# cpu_board_1.net
KiCad netlist of a schematic drawn in Altium Designer
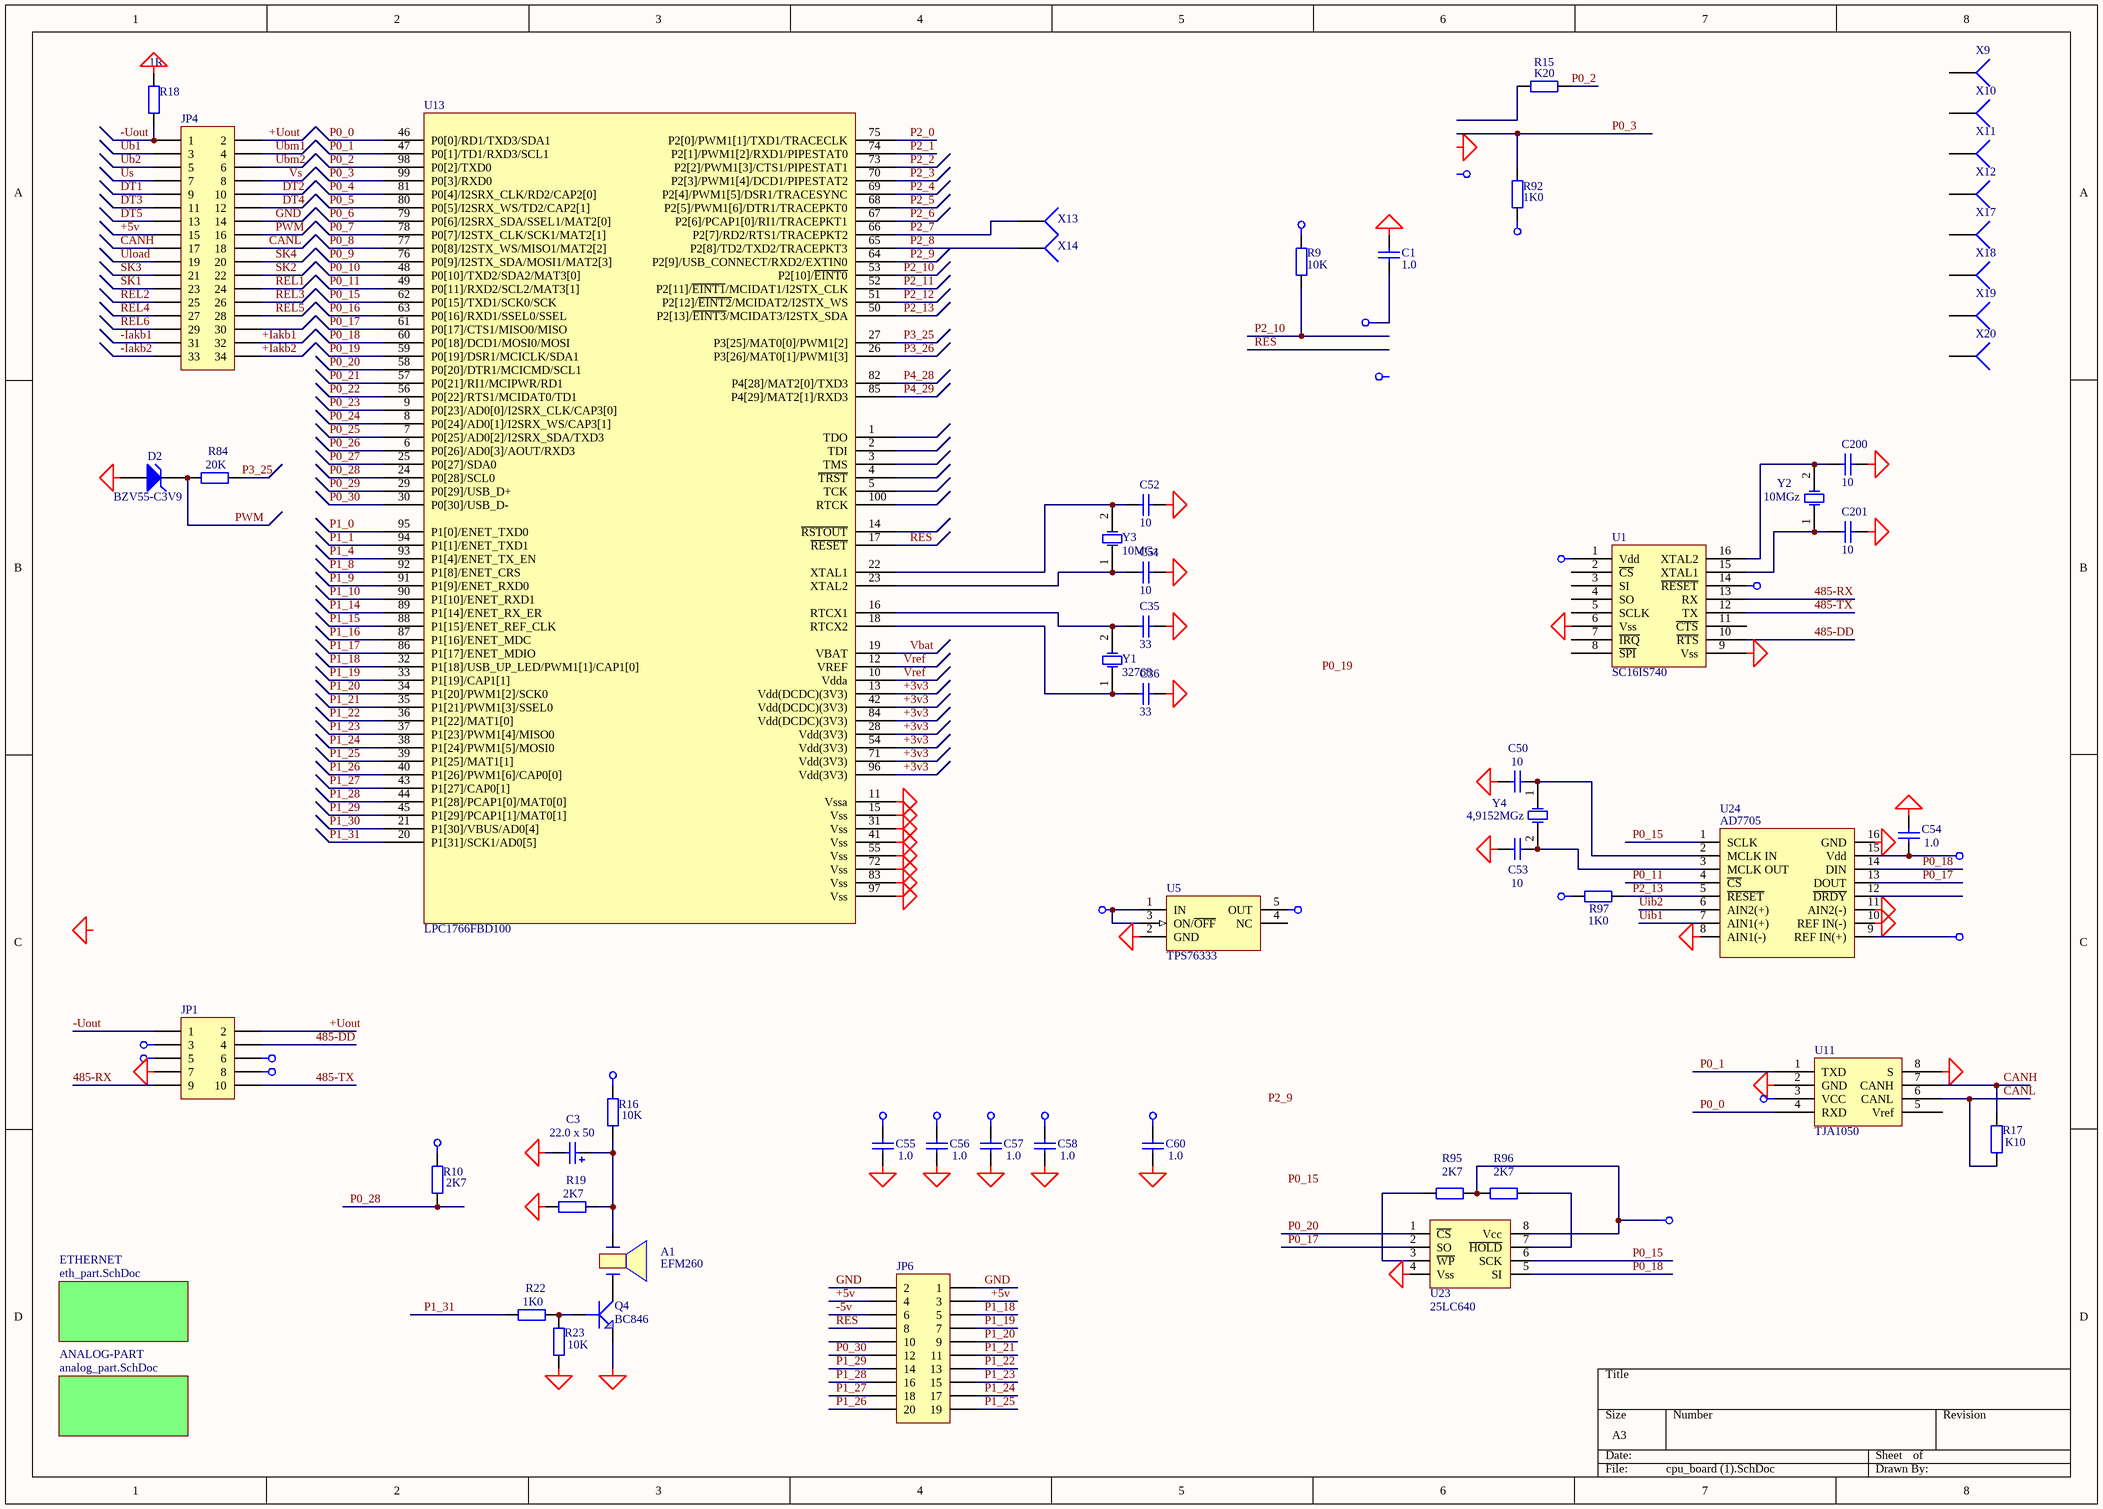
[diagram p0: cpu_board (1).SchDoc]

(export (version "E")
  (design (tool "Eeschema 10.0.6"))
  (components
    (comp (ref "A1")
      (value "EFM260")
      (footprint "Pjezo15")
      (description "Beeper")
      (libsource (lib "PAL") (part "PJEZ0"))
    )
    (comp (ref "C1")
      (value "1.0")
      (footprint "_1206")
      (description "Capacitor")
      (fields (field (name "MANUFACTURER") "Generic Components") (field (name "PUBLISHER") "Altium Limited"))
      (libsource (lib "Miscellaneous Devices") (part "Cap Semi"))
    )
    (comp (ref "C3")
      (value "22.0 x 50")
      (footprint "el3")
      (description "Polarized Capacitor (Radial)")
      (fields (field (name "MANUFACTURER") "Generic Components") (field (name "PUBLISHER") "Altium Limited"))
      (libsource (lib "PAL") (part "Cap Pol1"))
    )
    (comp (ref "C35")
      (value "33")
      (footprint "_1206")
      (description "Capacitor (Semiconductor SIM Model)")
      (fields (field (name "MANUFACTURER") "Generic Components") (field (name "PUBLISHER") "Altium Limited"))
      (libsource (lib "Miscellaneous Devices") (part "Cap Semi"))
    )
    (comp (ref "C36")
      (value "33")
      (footprint "_1206")
      (description "Capacitor (Semiconductor SIM Model)")
      (fields (field (name "MANUFACTURER") "Generic Components") (field (name "PUBLISHER") "Altium Limited"))
      (libsource (lib "Miscellaneous Devices") (part "Cap Semi"))
    )
    (comp (ref "C50")
      (value "10")
      (footprint "_1206")
      (description "Capacitor")
      (fields (field (name "MANUFACTURER") "Generic Components") (field (name "PUBLISHER") "Altium Limited"))
      (libsource (lib "") (part "Cap Semi_1"))
    )
    (comp (ref "C51")
      (value "10")
      (footprint "_1206")
      (description "Capacitor")
      (fields (field (name "MANUFACTURER") "Generic Components") (field (name "PUBLISHER") "Altium Limited"))
      (libsource (lib "Miscellaneous Devices") (part "Cap Semi"))
    )
    (comp (ref "C52")
      (value "10")
      (footprint "_1206")
      (description "Capacitor")
      (fields (field (name "MANUFACTURER") "Generic Components") (field (name "PUBLISHER") "Altium Limited"))
      (libsource (lib "Miscellaneous Devices") (part "Cap Semi"))
    )
    (comp (ref "C53")
      (value "10")
      (footprint "_1206")
      (description "Capacitor")
      (fields (field (name "MANUFACTURER") "Generic Components") (field (name "PUBLISHER") "Altium Limited"))
      (libsource (lib "") (part "Cap Semi_1"))
    )
    (comp (ref "C54")
      (value "1.0")
      (footprint "_1206")
      (description "Capacitor")
      (fields (field (name "MANUFACTURER") "Generic Components") (field (name "PUBLISHER") "Altium Limited"))
      (libsource (lib "Miscellaneous Devices") (part "Cap Semi"))
    )
    (comp (ref "C55")
      (value "1.0")
      (footprint "_1206")
      (description "Capacitor")
      (fields (field (name "MANUFACTURER") "Generic Components") (field (name "PUBLISHER") "Altium Limited"))
      (libsource (lib "Miscellaneous Devices") (part "Cap Semi"))
    )
    (comp (ref "C56")
      (value "1.0")
      (footprint "_1206")
      (description "Capacitor")
      (fields (field (name "MANUFACTURER") "Generic Components") (field (name "PUBLISHER") "Altium Limited"))
      (libsource (lib "Miscellaneous Devices") (part "Cap Semi"))
    )
    (comp (ref "C57")
      (value "1.0")
      (footprint "_1206")
      (description "Capacitor")
      (fields (field (name "MANUFACTURER") "Generic Components") (field (name "PUBLISHER") "Altium Limited"))
      (libsource (lib "Miscellaneous Devices") (part "Cap Semi"))
    )
    (comp (ref "C58")
      (value "1.0")
      (footprint "_1206")
      (description "Capacitor")
      (fields (field (name "MANUFACTURER") "Generic Components") (field (name "PUBLISHER") "Altium Limited"))
      (libsource (lib "Miscellaneous Devices") (part "Cap Semi"))
    )
    (comp (ref "C60")
      (value "1.0")
      (footprint "_1206")
      (description "Capacitor")
      (fields (field (name "MANUFACTURER") "Generic Components") (field (name "PUBLISHER") "Altium Limited"))
      (libsource (lib "Miscellaneous Devices") (part "Cap Semi"))
    )
    (comp (ref "C200")
      (value "10")
      (footprint "_1206")
      (description "Capacitor")
      (fields (field (name "MANUFACTURER") "Generic Components") (field (name "PUBLISHER") "Altium Limited"))
      (libsource (lib "Miscellaneous Devices") (part "Cap Semi"))
    )
    (comp (ref "C201")
      (value "10")
      (footprint "_1206")
      (description "Capacitor")
      (fields (field (name "MANUFACTURER") "Generic Components") (field (name "PUBLISHER") "Altium Limited"))
      (libsource (lib "Miscellaneous Devices") (part "Cap Semi"))
    )
    (comp (ref "D2")
      (value "BZV55-C3V9")
      (footprint "_1206d")
      (description "Zener Diode")
      (fields (field (name "MANUFACTURER") "Generic Components") (field (name "PUBLISHER") "Altium Limited"))
      (libsource (lib "Miscellaneous Devices") (part "D Zener"))
    )
    (comp (ref "JP1")
      (value "PBD-10")
      (footprint "HDR2X5")
      (description "Header, 5-Pin, Dual row")
      (fields (field (name "MANUFACTURER") "Generic Components") (field (name "PUBLISHER") "Altium Limited"))
      (libsource (lib "Miscellaneous Connectors") (part "Header 5X2"))
    )
    (comp (ref "JP4")
      (value "IDC34")
      (footprint "IDC34M")
      (description "Header, 17-Pin, Dual row")
      (fields (field (name "MANUFACTURER") "Generic Components") (field (name "PUBLISHER") "Altium Limited"))
      (libsource (lib "Miscellaneous Connectors") (part "Header 17X2"))
    )
    (comp (ref "JP6")
      (value "PBD-20")
      (footprint "HDR2X10")
      (description "Header, 10-Pin, Dual row")
      (fields (field (name "MANUFACTURER") "Generic Components") (field (name "PUBLISHER") "Altium Limited"))
      (libsource (lib "Miscellaneous Connectors") (part "Header 10X2"))
    )
    (comp (ref "Q4")
      (value "BC846")
      (footprint "SO-G3")
      (description "Bipolar transistor")
      (libsource (lib "MAIN") (part "GT122"))
    )
    (comp (ref "R9")
      (value "10K")
      (footprint "_1206")
      (description "Resistor")
      (fields (field (name "MANUFACTURER") "Generic Components") (field (name "PUBLISHER") "Altium Limited"))
      (libsource (lib "") (part "Res2_3"))
    )
    (comp (ref "R10")
      (value "2K7")
      (footprint "_1206")
      (description "Resistor")
      (fields (field (name "MANUFACTURER") "Generic Components") (field (name "PUBLISHER") "Altium Limited"))
      (libsource (lib "") (part "Res2_1"))
    )
    (comp (ref "R15")
      (value "K20")
      (footprint "_1206")
      (description "Resistor")
      (fields (field (name "MANUFACTURER") "Generic Components") (field (name "PUBLISHER") "Altium Limited"))
      (libsource (lib "Miscellaneous Devices") (part "Res2"))
    )
    (comp (ref "R16")
      (value "10K")
      (footprint "_1206")
      (description "Resistor")
      (fields (field (name "MANUFACTURER") "Generic Components") (field (name "PUBLISHER") "Altium Limited"))
      (libsource (lib "") (part "Res2_1"))
    )
    (comp (ref "R17")
      (value "K10")
      (footprint "_1206")
      (description "Resistor")
      (fields (field (name "MANUFACTURER") "Generic Components") (field (name "PUBLISHER") "Altium Limited"))
      (libsource (lib "") (part "Res2_1"))
    )
    (comp (ref "R18")
      (value "1R")
      (footprint "_1206")
      (description "Resistor")
      (fields (field (name "MANUFACTURER") "Generic Components") (field (name "PUBLISHER") "Altium Limited"))
      (libsource (lib "") (part "Res2_1"))
    )
    (comp (ref "R19")
      (value "2K7")
      (footprint "_1206")
      (description "Resistor")
      (fields (field (name "MANUFACTURER") "Generic Components") (field (name "PUBLISHER") "Altium Limited"))
      (libsource (lib "Miscellaneous Devices") (part "Res2"))
    )
    (comp (ref "R22")
      (value "1K0")
      (footprint "_1206")
      (description "Resistor")
      (fields (field (name "MANUFACTURER") "Generic Components") (field (name "PUBLISHER") "Altium Limited"))
      (libsource (lib "Miscellaneous Devices") (part "Res2"))
    )
    (comp (ref "R23")
      (value "10K")
      (footprint "_1206")
      (description "Resistor")
      (fields (field (name "MANUFACTURER") "Generic Components") (field (name "PUBLISHER") "Altium Limited"))
      (libsource (lib "") (part "Res2_1"))
    )
    (comp (ref "R84")
      (value "20K")
      (footprint "_1206")
      (description "Resistor")
      (fields (field (name "MANUFACTURER") "Generic Components") (field (name "PUBLISHER") "Altium Limited"))
      (libsource (lib "Miscellaneous Devices") (part "Res2"))
    )
    (comp (ref "R92")
      (value "1K0")
      (footprint "_1206")
      (description "Resistor")
      (fields (field (name "MANUFACTURER") "Generic Components") (field (name "PUBLISHER") "Altium Limited"))
      (libsource (lib "") (part "Res2_2"))
    )
    (comp (ref "R95")
      (value "2K7")
      (footprint "_1206")
      (description "Resistor")
      (fields (field (name "MANUFACTURER") "Generic Components") (field (name "PUBLISHER") "Altium Limited"))
      (libsource (lib "Miscellaneous Devices") (part "Res2"))
    )
    (comp (ref "R96")
      (value "2K7")
      (footprint "_1206")
      (description "Resistor")
      (fields (field (name "MANUFACTURER") "Generic Components") (field (name "PUBLISHER") "Altium Limited"))
      (libsource (lib "Miscellaneous Devices") (part "Res2"))
    )
    (comp (ref "R97")
      (value "1K0")
      (footprint "_1206")
      (description "Resistor")
      (fields (field (name "MANUFACTURER") "Generic Components") (field (name "PUBLISHER") "Altium Limited"))
      (libsource (lib "") (part "Res2_2"))
    )
    (comp (ref "U1") (value "SC16IS740") (footprint "SO-G16") (libsource (lib "PAL") (part "SC16IS740")))
    (comp (ref "U5")
      (value "TPS76333")
      (footprint "SO-G5/P.95")
      (description "Voltage Regulator")
      (fields
        (field (name "MANUFACTURER") "National Semiconductor")
        (field (name "PUBLISHER") "Altium Limited")
      )
      (libsource (lib "NSC Power Mgt Voltage Regulator") (part "LP2980AIM5-3.3"))
    )
    (comp (ref "U11") (value "TJA1050") (footprint "SO-G8/D5") (libsource (lib "PAL") (part "TJA1050")))
    (comp (ref "U13")
      (value "LPC1766FBD100")
      (footprint "LPC2368")
      (libsource (lib "PAL") (part "LPC2368FBD100"))
    )
    (comp (ref "U23")
      (value "25LC640")
      (footprint "SO-G8/D5")
      (description "Memory")
      (libsource (lib "PAL") (part "25LC640"))
    )
    (comp (ref "U24")
      (value "AD7705")
      (footprint "SO-G16/D10.4")
      (description "ADC")
      (libsource (lib "PAL") (part "AD7705"))
    )
    (comp (ref "X9")
      (value "~")
      (footprint "PIN1")
      (description "Socket")
      (fields (field (name "MANUFACTURER") "Generic Components") (field (name "PUBLISHER") "Altium Limited"))
      (libsource (lib "Miscellaneous Connectors") (part "Socket"))
    )
    (comp (ref "X10")
      (value "~")
      (footprint "PIN1")
      (description "Socket")
      (fields (field (name "MANUFACTURER") "Generic Components") (field (name "PUBLISHER") "Altium Limited"))
      (libsource (lib "Miscellaneous Connectors") (part "Socket"))
    )
    (comp (ref "X11")
      (value "~")
      (footprint "PIN1")
      (description "Socket")
      (fields (field (name "MANUFACTURER") "Generic Components") (field (name "PUBLISHER") "Altium Limited"))
      (libsource (lib "Miscellaneous Connectors") (part "Socket"))
    )
    (comp (ref "X12")
      (value "~")
      (footprint "PIN1")
      (description "Socket")
      (fields (field (name "MANUFACTURER") "Generic Components") (field (name "PUBLISHER") "Altium Limited"))
      (libsource (lib "Miscellaneous Connectors") (part "Socket"))
    )
    (comp (ref "X13")
      (value "~")
      (footprint "PIN1")
      (description "Socket")
      (fields (field (name "MANUFACTURER") "Generic Components") (field (name "PUBLISHER") "Altium Limited"))
      (libsource (lib "Miscellaneous Connectors") (part "Socket"))
    )
    (comp (ref "X14")
      (value "~")
      (footprint "PIN1")
      (description "Socket")
      (fields (field (name "MANUFACTURER") "Generic Components") (field (name "PUBLISHER") "Altium Limited"))
      (libsource (lib "Miscellaneous Connectors") (part "Socket"))
    )
    (comp (ref "X17")
      (value "~")
      (footprint "PIN1")
      (description "Socket")
      (fields (field (name "MANUFACTURER") "Generic Components") (field (name "PUBLISHER") "Altium Limited"))
      (libsource (lib "Miscellaneous Connectors") (part "Socket"))
    )
    (comp (ref "X18")
      (value "~")
      (footprint "PIN1")
      (description "Socket")
      (fields (field (name "MANUFACTURER") "Generic Components") (field (name "PUBLISHER") "Altium Limited"))
      (libsource (lib "Miscellaneous Connectors") (part "Socket"))
    )
    (comp (ref "X19")
      (value "~")
      (footprint "PIN1")
      (description "Socket")
      (fields (field (name "MANUFACTURER") "Generic Components") (field (name "PUBLISHER") "Altium Limited"))
      (libsource (lib "Miscellaneous Connectors") (part "Socket"))
    )
    (comp (ref "X20")
      (value "~")
      (footprint "PIN1")
      (description "Socket")
      (fields (field (name "MANUFACTURER") "Generic Components") (field (name "PUBLISHER") "Altium Limited"))
      (libsource (lib "Miscellaneous Connectors") (part "Socket"))
    )
    (comp (ref "Y1")
      (value "32768")
      (footprint "QWARZ2")
      (description "Crystal Oscillator")
      (fields (field (name "MANUFACTURER") "Generic Components") (field (name "PUBLISHER") "Altium Limited"))
      (libsource (lib "") (part "XTAL_1"))
    )
    (comp (ref "Y2")
      (value "10MGz")
      (footprint "QWARZ1")
      (description "Crystal Oscillator")
      (fields (field (name "MANUFACTURER") "Generic Components") (field (name "PUBLISHER") "Altium Limited"))
      (libsource (lib "") (part "XTAL_1"))
    )
    (comp (ref "Y3")
      (value "10MGz")
      (footprint "QWARZ1")
      (description "Crystal Oscillator")
      (fields (field (name "MANUFACTURER") "Generic Components") (field (name "PUBLISHER") "Altium Limited"))
      (libsource (lib "") (part "XTAL_1"))
    )
    (comp (ref "Y4")
      (value "4,9152MGz")
      (footprint "QWARZ1")
      (description "Crystal Oscillator")
      (fields (field (name "MANUFACTURER") "Generic Components") (field (name "PUBLISHER") "Altium Limited"))
      (libsource (lib "Miscellaneous Devices") (part "XTAL"))
    )
  )
  (nets
    (net (code "1") (name "+3v3") (class "Default")
      (node (ref "C1") (pin "1") (pinfunction "1_1") (pintype "passive"))
      (node (ref "C58") (pin "2") (pinfunction "2_2") (pintype "passive"))
      (node (ref "JP1") (pin "3") (pinfunction "3_3") (pintype "passive"))
      (node (ref "R10") (pin "2") (pinfunction "2_2") (pintype "passive"))
      (node (ref "R9") (pin "1") (pinfunction "1_1") (pintype "passive"))
      (node (ref "R92") (pin "2") (pinfunction "2_2") (pintype "passive"))
      (node (ref "U13") (pin "13") (pinfunction "Vdd(DCDC)(3V3)_13") (pintype "passive"))
      (node (ref "U13") (pin "28") (pinfunction "Vdd(3V3)_28") (pintype "passive"))
      (node (ref "U13") (pin "42") (pinfunction "Vdd(DCDC)(3V3)_42") (pintype "passive"))
      (node (ref "U13") (pin "54") (pinfunction "Vdd(3V3)_54") (pintype "passive"))
      (node (ref "U13") (pin "71") (pinfunction "Vdd(3V3)_71") (pintype "passive"))
      (node (ref "U13") (pin "84") (pinfunction "Vdd(DCDC)(3V3)_84") (pintype "passive"))
      (node (ref "U13") (pin "96") (pinfunction "Vdd(3V3)_96") (pintype "passive"))
    )
    (net (code "2") (name "+5v") (class "Default")
      (node (ref "C54") (pin "2") (pinfunction "2_2") (pintype "passive"))
      (node (ref "C55") (pin "2") (pinfunction "2_2") (pintype "passive"))
      (node (ref "C57") (pin "2") (pinfunction "2_2") (pintype "passive"))
      (node (ref "C60") (pin "2") (pinfunction "2_2") (pintype "passive"))
      (node (ref "JP1") (pin "5") (pinfunction "5_5") (pintype "passive"))
      (node (ref "JP4") (pin "15") (pinfunction "15_15") (pintype "passive"))
      (node (ref "JP6") (pin "3") (pinfunction "3_3") (pintype "passive"))
      (node (ref "JP6") (pin "4") (pinfunction "4_4") (pintype "passive"))
      (node (ref "R95") (pin "2") (pinfunction "2_2") (pintype "passive"))
      (node (ref "R96") (pin "1") (pinfunction "1_1") (pintype "passive"))
      (node (ref "R97") (pin "2") (pinfunction "2_2") (pintype "passive"))
      (node (ref "U1") (pin "1") (pinfunction "Vdd_1") (pintype "passive"))
      (node (ref "U1") (pin "14") (pinfunction "~{RESET}_14") (pintype "passive"))
      (node (ref "U11") (pin "3") (pinfunction "VCC_3") (pintype "passive"))
      (node (ref "U23") (pin "8") (pinfunction "Vcc_8") (pintype "passive"))
      (node (ref "U24") (pin "15") (pinfunction "Vdd_15") (pintype "passive"))
      (node (ref "U5") (pin "1") (pinfunction "IN_1") (pintype "power_in"))
      (node (ref "U5") (pin "3") (pinfunction "ON/~{OFF}_3") (pintype "input"))
    )
    (net (code "4") (name "+Uout") (class "Default")
      (node (ref "JP1") (pin "2") (pinfunction "2_2") (pintype "passive"))
      (node (ref "JP4") (pin "2") (pinfunction "2_2") (pintype "passive"))
      (node (ref "R16") (pin "2") (pinfunction "2_2") (pintype "passive"))
    )
    (net (code "5") (name "-5v") (class "Default")
      (node (ref "C56") (pin "2") (pinfunction "2_2") (pintype "passive"))
      (node (ref "JP1") (pin "8") (pinfunction "8_8") (pintype "passive"))
      (node (ref "JP6") (pin "6") (pinfunction "6_6") (pintype "passive"))
    )
    (net (code "7") (name "/+Iakb1") (class "Default")
      (node (ref "JP4") (pin "32") (pinfunction "32_32") (pintype "passive"))
    )
    (net (code "8") (name "/+Iakb2") (class "Default")
      (node (ref "JP4") (pin "34") (pinfunction "34_34") (pintype "passive"))
    )
    (net (code "9") (name "/-Iakb1") (class "Default")
      (node (ref "JP4") (pin "31") (pinfunction "31_31") (pintype "passive"))
    )
    (net (code "10") (name "/-Iakb2") (class "Default")
      (node (ref "JP4") (pin "33") (pinfunction "33_33") (pintype "passive"))
    )
    (net (code "11") (name "/-Uout") (class "Default")
      (node (ref "JP1") (pin "1") (pinfunction "1_1") (pintype "passive"))
      (node (ref "JP4") (pin "1") (pinfunction "1_1") (pintype "passive"))
      (node (ref "R18") (pin "1") (pinfunction "1_1") (pintype "passive"))
    )
    (net (code "12") (name "/485-DD") (class "Default")
      (node (ref "JP1") (pin "4") (pinfunction "4_4") (pintype "passive"))
      (node (ref "U1") (pin "10") (pinfunction "~{RTS}_10") (pintype "passive"))
    )
    (net (code "13") (name "/485-RX") (class "Default")
      (node (ref "JP1") (pin "9") (pinfunction "9_9") (pintype "passive"))
      (node (ref "U1") (pin "13") (pinfunction "RX_13") (pintype "passive"))
    )
    (net (code "14") (name "/485-TX") (class "Default")
      (node (ref "JP1") (pin "10") (pinfunction "10_10") (pintype "passive"))
      (node (ref "U1") (pin "12") (pinfunction "TX_12") (pintype "passive"))
    )
    (net (code "15") (name "/CANH") (class "Default")
      (node (ref "JP4") (pin "17") (pinfunction "17_17") (pintype "passive"))
      (node (ref "R17") (pin "2") (pinfunction "2_2") (pintype "passive"))
      (node (ref "U11") (pin "7") (pinfunction "CANH_7") (pintype "passive"))
    )
    (net (code "16") (name "/CANL") (class "Default")
      (node (ref "JP4") (pin "18") (pinfunction "18_18") (pintype "passive"))
      (node (ref "R17") (pin "1") (pinfunction "1_1") (pintype "passive"))
      (node (ref "U11") (pin "6") (pinfunction "CANL_6") (pintype "passive"))
    )
    (net (code "17") (name "/DT1") (class "Default")
      (node (ref "JP4") (pin "9") (pinfunction "9_9") (pintype "passive"))
    )
    (net (code "18") (name "/DT2") (class "Default")
      (node (ref "JP4") (pin "10") (pinfunction "10_10") (pintype "passive"))
    )
    (net (code "19") (name "/DT3") (class "Default")
      (node (ref "JP4") (pin "11") (pinfunction "11_11") (pintype "passive"))
    )
    (net (code "20") (name "/DT4") (class "Default")
      (node (ref "JP4") (pin "12") (pinfunction "12_12") (pintype "passive"))
    )
    (net (code "21") (name "/DT5") (class "Default")
      (node (ref "JP4") (pin "13") (pinfunction "13_13") (pintype "passive"))
    )
    (net (code "22") (name "/P0_0") (class "Default")
      (node (ref "U11") (pin "4") (pinfunction "RXD_4") (pintype "passive"))
      (node (ref "U13") (pin "46") (pinfunction "P0[0]/RD1/TXD3/SDA1_46") (pintype "passive"))
    )
    (net (code "23") (name "/P0_1") (class "Default")
      (node (ref "U11") (pin "1") (pinfunction "TXD_1") (pintype "passive"))
      (node (ref "U13") (pin "47") (pinfunction "P0[1]/TD1/RXD3/SCL1_47") (pintype "passive"))
    )
    (net (code "24") (name "/P0_2") (class "Default")
      (node (ref "R15") (pin "2") (pinfunction "2_2") (pintype "passive"))
      (node (ref "U13") (pin "98") (pinfunction "P0[2]/TXD0_98") (pintype "passive"))
    )
    (net (code "25") (name "/P0_3") (class "Default")
      (node (ref "R92") (pin "1") (pinfunction "1_1") (pintype "passive"))
      (node (ref "U13") (pin "99") (pinfunction "P0[3]/RXD0_99") (pintype "passive"))
    )
    (net (code "26") (name "/P0_4") (class "Default")
      (node (ref "U13") (pin "81") (pinfunction "P0[4]/I2SRX_CLK/RD2/CAP2[0]_81") (pintype "passive"))
    )
    (net (code "27") (name "/P0_5") (class "Default")
      (node (ref "U13") (pin "80") (pinfunction "P0[5]/I2SRX_WS/TD2/CAP2[1]_80") (pintype "passive"))
    )
    (net (code "28") (name "/P0_6") (class "Default")
      (node (ref "U13") (pin "79") (pinfunction "P0[6]/I2SRX_SDA/SSEL1/MAT2[0]_79") (pintype "passive"))
    )
    (net (code "29") (name "/P0_7") (class "Default")
      (node (ref "U13") (pin "78") (pinfunction "P0[7]/I2STX_CLK/SCK1/MAT2[1]_78") (pintype "passive"))
    )
    (net (code "30") (name "/P0_8") (class "Default")
      (node (ref "U13") (pin "77") (pinfunction "P0[8]/I2STX_WS/MISO1/MAT2[2]_77") (pintype "passive"))
    )
    (net (code "31") (name "/P0_9") (class "Default")
      (node (ref "U13") (pin "76") (pinfunction "P0[9]/I2STX_SDA/MOSI1/MAT2[3]_76") (pintype "passive"))
    )
    (net (code "32") (name "/P0_10") (class "Default")
      (node (ref "U13") (pin "48") (pinfunction "P0[10]/TXD2/SDA2/MAT3[0]_48") (pintype "passive"))
    )
    (net (code "33") (name "/P0_11") (class "Default")
      (node (ref "U13") (pin "49") (pinfunction "P0[11]/RXD2/SCL2/MAT3[1]_49") (pintype "passive"))
      (node (ref "U24") (pin "4") (pinfunction "~{CS}_4") (pintype "passive"))
    )
    (net (code "34") (name "/P0_15") (class "Default")
      (node (ref "U13") (pin "62") (pinfunction "P0[15]/TXD1/SCK0/SCK_62") (pintype "passive"))
      (node (ref "U23") (pin "6") (pinfunction "SCK_6") (pintype "passive"))
      (node (ref "U24") (pin "1") (pinfunction "SCLK_1") (pintype "passive"))
    )
    (net (code "35") (name "/P0_16") (class "Default")
      (node (ref "U13") (pin "63") (pinfunction "P0[16]/RXD1/SSEL0/SSEL_63") (pintype "passive"))
    )
    (net (code "36") (name "/P0_17") (class "Default")
      (node (ref "U13") (pin "61") (pinfunction "P0[17]/CTS1/MISO0/MISO_61") (pintype "passive"))
      (node (ref "U23") (pin "2") (pinfunction "SO_2") (pintype "passive"))
      (node (ref "U24") (pin "13") (pinfunction "DOUT_13") (pintype "passive"))
    )
    (net (code "37") (name "/P0_18") (class "Default")
      (node (ref "U13") (pin "60") (pinfunction "P0[18]/DCD1/MOSI0/MOSI_60") (pintype "passive"))
      (node (ref "U23") (pin "5") (pinfunction "SI_5") (pintype "passive"))
      (node (ref "U24") (pin "14") (pinfunction "DIN_14") (pintype "passive"))
    )
    (net (code "38") (name "/P0_19") (class "Default")
      (node (ref "U13") (pin "59") (pinfunction "P0[19]/DSR1/MCICLK/SDA1_59") (pintype "passive"))
    )
    (net (code "39") (name "/P0_20") (class "Default")
      (node (ref "U13") (pin "58") (pinfunction "P0[20]/DTR1/MCICMD/SCL1_58") (pintype "passive"))
      (node (ref "U23") (pin "1") (pinfunction "~{CS}_1") (pintype "passive"))
    )
    (net (code "40") (name "/P0_21") (class "Default")
      (node (ref "U13") (pin "57") (pinfunction "P0[21]/RI1/MCIPWR/RD1_57") (pintype "passive"))
    )
    (net (code "41") (name "/P0_22") (class "Default")
      (node (ref "U13") (pin "56") (pinfunction "P0[22]/RTS1/MCIDAT0/TD1_56") (pintype "passive"))
    )
    (net (code "42") (name "/P0_23") (class "Default")
      (node (ref "U13") (pin "9") (pinfunction "P0[23]/AD0[0]/I2SRX_CLK/CAP3[0]_9") (pintype "passive"))
    )
    (net (code "43") (name "/P0_24") (class "Default")
      (node (ref "U13") (pin "8") (pinfunction "P0[24]/AD0[1]/I2SRX_WS/CAP3[1]_8") (pintype "passive"))
    )
    (net (code "44") (name "/P0_25") (class "Default")
      (node (ref "U13") (pin "7") (pinfunction "P0[25]/AD0[2]/I2SRX_SDA/TXD3_7") (pintype "passive"))
    )
    (net (code "45") (name "/P0_26") (class "Default")
      (node (ref "U13") (pin "6") (pinfunction "P0[26]/AD0[3]/AOUT/RXD3_6") (pintype "passive"))
    )
    (net (code "46") (name "/P0_27") (class "Default")
      (node (ref "U13") (pin "25") (pinfunction "P0[27]/SDA0_25") (pintype "passive"))
    )
    (net (code "47") (name "/P0_28") (class "Default")
      (node (ref "R10") (pin "1") (pinfunction "1_1") (pintype "passive"))
      (node (ref "U13") (pin "24") (pinfunction "P0[28]/SCL0_24") (pintype "passive"))
    )
    (net (code "48") (name "/P0_29") (class "Default")
      (node (ref "U13") (pin "29") (pinfunction "P0[29]/USB_D+_29") (pintype "passive"))
    )
    (net (code "49") (name "/P0_30") (class "Default")
      (node (ref "JP6") (pin "12") (pinfunction "12_12") (pintype "passive"))
      (node (ref "U13") (pin "30") (pinfunction "P0[30]/USB_D-_30") (pintype "passive"))
    )
    (net (code "50") (name "/P1_0") (class "Default")
      (node (ref "U13") (pin "95") (pinfunction "P1[0]/ENET_TXD0_95") (pintype "passive"))
    )
    (net (code "51") (name "/P1_1") (class "Default")
      (node (ref "U13") (pin "94") (pinfunction "P1[1]/ENET_TXD1_94") (pintype "passive"))
    )
    (net (code "52") (name "/P1_4") (class "Default")
      (node (ref "U13") (pin "93") (pinfunction "P1[4]/ENET_TX_EN_93") (pintype "passive"))
    )
    (net (code "53") (name "/P1_8") (class "Default")
      (node (ref "U13") (pin "92") (pinfunction "P1[8]/ENET_CRS_92") (pintype "passive"))
    )
    (net (code "54") (name "/P1_9") (class "Default")
      (node (ref "U13") (pin "91") (pinfunction "P1[9]/ENET_RXD0_91") (pintype "passive"))
    )
    (net (code "55") (name "/P1_10") (class "Default")
      (node (ref "U13") (pin "90") (pinfunction "P1[10]/ENET_RXD1_90") (pintype "passive"))
    )
    (net (code "56") (name "/P1_14") (class "Default")
      (node (ref "U13") (pin "89") (pinfunction "P1[14]/ENET_RX_ER_89") (pintype "passive"))
    )
    (net (code "57") (name "/P1_15") (class "Default")
      (node (ref "U13") (pin "88") (pinfunction "P1[15]/ENET_REF_CLK_88") (pintype "passive"))
    )
    (net (code "58") (name "/P1_16") (class "Default")
      (node (ref "U13") (pin "87") (pinfunction "P1[16]/ENET_MDC_87") (pintype "passive"))
    )
    (net (code "59") (name "/P1_17") (class "Default")
      (node (ref "U13") (pin "86") (pinfunction "P1[17]/ENET_MDIO_86") (pintype "passive"))
    )
    (net (code "60") (name "/P1_18") (class "Default")
      (node (ref "JP6") (pin "5") (pinfunction "5_5") (pintype "passive"))
      (node (ref "U13") (pin "32") (pinfunction "P1[18]/USB_UP_LED/PWM1[1]/CAP1[0]_32") (pintype "passive"))
    )
    (net (code "61") (name "/P1_19") (class "Default")
      (node (ref "JP6") (pin "7") (pinfunction "7_7") (pintype "passive"))
      (node (ref "U13") (pin "33") (pinfunction "P1[19]/CAP1[1]_33") (pintype "passive"))
    )
    (net (code "62") (name "/P1_20") (class "Default")
      (node (ref "JP6") (pin "9") (pinfunction "9_9") (pintype "passive"))
      (node (ref "U13") (pin "34") (pinfunction "P1[20]/PWM1[2]/SCK0_34") (pintype "passive"))
    )
    (net (code "63") (name "/P1_21") (class "Default")
      (node (ref "JP6") (pin "11") (pinfunction "11_11") (pintype "passive"))
      (node (ref "U13") (pin "35") (pinfunction "P1[21]/PWM1[3]/SSEL0_35") (pintype "passive"))
    )
    (net (code "64") (name "/P1_22") (class "Default")
      (node (ref "JP6") (pin "13") (pinfunction "13_13") (pintype "passive"))
      (node (ref "U13") (pin "36") (pinfunction "P1[22]/MAT1[0]_36") (pintype "passive"))
    )
    (net (code "65") (name "/P1_23") (class "Default")
      (node (ref "JP6") (pin "15") (pinfunction "15_15") (pintype "passive"))
      (node (ref "U13") (pin "37") (pinfunction "P1[23]/PWM1[4]/MISO0_37") (pintype "passive"))
    )
    (net (code "66") (name "/P1_24") (class "Default")
      (node (ref "JP6") (pin "17") (pinfunction "17_17") (pintype "passive"))
      (node (ref "U13") (pin "38") (pinfunction "P1[24]/PWM1[5]/MOSI0_38") (pintype "passive"))
    )
    (net (code "67") (name "/P1_25") (class "Default")
      (node (ref "JP6") (pin "19") (pinfunction "19_19") (pintype "passive"))
      (node (ref "U13") (pin "39") (pinfunction "P1[25]/MAT1[1]_39") (pintype "passive"))
    )
    (net (code "68") (name "/P1_26") (class "Default")
      (node (ref "JP6") (pin "20") (pinfunction "20_20") (pintype "passive"))
      (node (ref "U13") (pin "40") (pinfunction "P1[26]/PWM1[6]/CAP0[0]_40") (pintype "passive"))
    )
    (net (code "69") (name "/P1_27") (class "Default")
      (node (ref "JP6") (pin "18") (pinfunction "18_18") (pintype "passive"))
      (node (ref "U13") (pin "43") (pinfunction "P1[27]/CAP0[1]_43") (pintype "passive"))
    )
    (net (code "70") (name "/P1_28") (class "Default")
      (node (ref "JP6") (pin "16") (pinfunction "16_16") (pintype "passive"))
      (node (ref "U13") (pin "44") (pinfunction "P1[28]/PCAP1[0]/MAT0[0]_44") (pintype "passive"))
    )
    (net (code "71") (name "/P1_29") (class "Default")
      (node (ref "JP6") (pin "14") (pinfunction "14_14") (pintype "passive"))
      (node (ref "U13") (pin "45") (pinfunction "P1[29]/PCAP1[1]/MAT0[1]_45") (pintype "passive"))
    )
    (net (code "72") (name "/P1_30") (class "Default")
      (node (ref "U13") (pin "21") (pinfunction "P1[30]/VBUS/AD0[4]_21") (pintype "passive"))
    )
    (net (code "73") (name "/P1_31") (class "Default")
      (node (ref "R22") (pin "1") (pinfunction "1_1") (pintype "passive"))
      (node (ref "U13") (pin "20") (pinfunction "P1[31]/SCK1/AD0[5]_20") (pintype "passive"))
    )
    (net (code "74") (name "/P2_0") (class "Default")
      (node (ref "U13") (pin "75") (pinfunction "P2[0]/PWM1[1]/TXD1/TRACECLK_75") (pintype "passive"))
    )
    (net (code "75") (name "/P2_1") (class "Default")
      (node (ref "U13") (pin "74") (pinfunction "P2[1]/PWM1[2]/RXD1/PIPESTAT0_74") (pintype "passive"))
    )
    (net (code "76") (name "/P2_2") (class "Default")
      (node (ref "U13") (pin "73") (pinfunction "P2[2]/PWM1[3]/CTS1/PIPESTAT1_73") (pintype "passive"))
    )
    (net (code "77") (name "/P2_3") (class "Default")
      (node (ref "U13") (pin "70") (pinfunction "P2[3]/PWM1[4]/DCD1/PIPESTAT2_70") (pintype "passive"))
    )
    (net (code "78") (name "/P2_4") (class "Default")
      (node (ref "U13") (pin "69") (pinfunction "P2[4]/PWM1[5]/DSR1/TRACESYNC_69") (pintype "passive"))
    )
    (net (code "79") (name "/P2_5") (class "Default")
      (node (ref "U13") (pin "68") (pinfunction "P2[5]/PWM1[6]/DTR1/TRACEPKT0_68") (pintype "passive"))
    )
    (net (code "80") (name "/P2_6") (class "Default")
      (node (ref "U13") (pin "67") (pinfunction "P2[6]/PCAP1[0]/RI1/TRACEPKT1_67") (pintype "passive"))
    )
    (net (code "81") (name "/P2_7") (class "Default")
      (node (ref "U13") (pin "66") (pinfunction "P2[7]/RD2/RTS1/TRACEPKT2_66") (pintype "passive"))
      (node (ref "X13") (pin "1") (pinfunction "1_1") (pintype "passive"))
    )
    (net (code "82") (name "/P2_8") (class "Default")
      (node (ref "U13") (pin "65") (pinfunction "P2[8]/TD2/TXD2/TRACEPKT3_65") (pintype "passive"))
      (node (ref "X14") (pin "1") (pinfunction "1_1") (pintype "passive"))
    )
    (net (code "83") (name "/P2_9") (class "Default")
      (node (ref "U13") (pin "64") (pinfunction "P2[9]/USB_CONNECT/RXD2/EXTIN0_64") (pintype "passive"))
    )
    (net (code "84") (name "/P2_10") (class "Default")
      (node (ref "R9") (pin "2") (pinfunction "2_2") (pintype "passive"))
      (node (ref "U13") (pin "53") (pinfunction "P2[10]/~{EINT0}_53") (pintype "passive"))
    )
    (net (code "85") (name "/P2_11") (class "Default")
      (node (ref "U13") (pin "52") (pinfunction "P2[11]/~{EINT1}/MCIDAT1/I2STX_CLK_52") (pintype "passive"))
    )
    (net (code "86") (name "/P2_12") (class "Default")
      (node (ref "U13") (pin "51") (pinfunction "P2[12]/~{EINT2}/MCIDAT2/I2STX_WS_51") (pintype "passive"))
    )
    (net (code "87") (name "/P2_13") (class "Default")
      (node (ref "R97") (pin "1") (pinfunction "1_1") (pintype "passive"))
      (node (ref "U13") (pin "50") (pinfunction "P2[13]/~{EINT3}/MCIDAT3/I2STX_SDA_50") (pintype "passive"))
      (node (ref "U24") (pin "5") (pinfunction "~{RESET}_5") (pintype "passive"))
    )
    (net (code "88") (name "/P3_25") (class "Default")
      (node (ref "R84") (pin "2") (pinfunction "2_2") (pintype "passive"))
      (node (ref "U13") (pin "27") (pinfunction "P3[25]/MAT0[0]/PWM1[2]_27") (pintype "passive"))
    )
    (net (code "89") (name "/P3_26") (class "Default")
      (node (ref "U13") (pin "26") (pinfunction "P3[26]/MAT0[1]/PWM1[3]_26") (pintype "passive"))
    )
    (net (code "90") (name "/P4_28") (class "Default")
      (node (ref "U13") (pin "82") (pinfunction "P4[28]/MAT2[0]/TXD3_82") (pintype "passive"))
    )
    (net (code "91") (name "/P4_29") (class "Default")
      (node (ref "U13") (pin "85") (pinfunction "P4[29]/MAT2[1]/RXD3_85") (pintype "passive"))
    )
    (net (code "92") (name "/PWM") (class "Default")
      (node (ref "D2") (pin "2") (pinfunction "K_2") (pintype "passive"))
      (node (ref "JP4") (pin "16") (pinfunction "16_16") (pintype "passive"))
      (node (ref "R84") (pin "1") (pinfunction "1_1") (pintype "passive"))
    )
    (net (code "93") (name "/REL1") (class "Default")
      (node (ref "JP4") (pin "24") (pinfunction "24_24") (pintype "passive"))
    )
    (net (code "94") (name "/REL2") (class "Default")
      (node (ref "JP4") (pin "25") (pinfunction "25_25") (pintype "passive"))
    )
    (net (code "95") (name "/REL3") (class "Default")
      (node (ref "JP4") (pin "26") (pinfunction "26_26") (pintype "passive"))
    )
    (net (code "96") (name "/REL4") (class "Default")
      (node (ref "JP4") (pin "27") (pinfunction "27_27") (pintype "passive"))
    )
    (net (code "97") (name "/REL5") (class "Default")
      (node (ref "JP4") (pin "28") (pinfunction "28_28") (pintype "passive"))
    )
    (net (code "98") (name "/REL6") (class "Default")
      (node (ref "JP4") (pin "29") (pinfunction "29_29") (pintype "passive"))
    )
    (net (code "99") (name "/RES") (class "Default")
      (node (ref "JP6") (pin "8") (pinfunction "8_8") (pintype "passive"))
      (node (ref "U13") (pin "17") (pinfunction "~{RESET}_17") (pintype "passive"))
    )
    (net (code "100") (name "/SK1") (class "Default")
      (node (ref "JP4") (pin "23") (pinfunction "23_23") (pintype "passive"))
    )
    (net (code "101") (name "/SK2") (class "Default")
      (node (ref "JP4") (pin "22") (pinfunction "22_22") (pintype "passive"))
    )
    (net (code "102") (name "/SK3") (class "Default")
      (node (ref "JP4") (pin "21") (pinfunction "21_21") (pintype "passive"))
    )
    (net (code "103") (name "/SK4") (class "Default")
      (node (ref "JP4") (pin "20") (pinfunction "20_20") (pintype "passive"))
    )
    (net (code "104") (name "/Ub1") (class "Default")
      (node (ref "JP4") (pin "3") (pinfunction "3_3") (pintype "passive"))
    )
    (net (code "105") (name "/Ub2") (class "Default")
      (node (ref "JP4") (pin "5") (pinfunction "5_5") (pintype "passive"))
    )
    (net (code "106") (name "/Ubm1") (class "Default")
      (node (ref "JP4") (pin "4") (pinfunction "4_4") (pintype "passive"))
    )
    (net (code "107") (name "/Ubm2") (class "Default")
      (node (ref "JP4") (pin "6") (pinfunction "6_6") (pintype "passive"))
    )
    (net (code "108") (name "/Uib1") (class "Default")
      (node (ref "U24") (pin "7") (pinfunction "AIN1(+)_7") (pintype "passive"))
    )
    (net (code "109") (name "/Uib2") (class "Default")
      (node (ref "U24") (pin "6") (pinfunction "AIN2(+)_6") (pintype "passive"))
    )
    (net (code "110") (name "/Uload") (class "Default")
      (node (ref "JP4") (pin "19") (pinfunction "19_19") (pintype "passive"))
    )
    (net (code "111") (name "/Us") (class "Default")
      (node (ref "JP4") (pin "7") (pinfunction "7_7") (pintype "passive"))
    )
    (net (code "112") (name "/Vs") (class "Default")
      (node (ref "JP4") (pin "8") (pinfunction "8_8") (pintype "passive"))
    )
    (net (code "113") (name "GND") (class "Default")
      (node (ref "C1") (pin "2") (pinfunction "2_2") (pintype "passive"))
      (node (ref "C200") (pin "1") (pinfunction "1_1") (pintype "passive"))
      (node (ref "C201") (pin "1") (pinfunction "1_1") (pintype "passive"))
      (node (ref "C3") (pin "2") (pinfunction "2_2") (pintype "passive"))
      (node (ref "C35") (pin "1") (pinfunction "1_1") (pintype "passive"))
      (node (ref "C36") (pin "1") (pinfunction "1_1") (pintype "passive"))
      (node (ref "C50") (pin "1") (pinfunction "1_1") (pintype "passive"))
      (node (ref "C51") (pin "1") (pinfunction "1_1") (pintype "passive"))
      (node (ref "C52") (pin "1") (pinfunction "1_1") (pintype "passive"))
      (node (ref "C53") (pin "1") (pinfunction "1_1") (pintype "passive"))
      (node (ref "C54") (pin "1") (pinfunction "1_1") (pintype "passive"))
      (node (ref "C55") (pin "1") (pinfunction "1_1") (pintype "passive"))
      (node (ref "C56") (pin "1") (pinfunction "1_1") (pintype "passive"))
      (node (ref "C57") (pin "1") (pinfunction "1_1") (pintype "passive"))
      (node (ref "C58") (pin "1") (pinfunction "1_1") (pintype "passive"))
      (node (ref "C60") (pin "1") (pinfunction "1_1") (pintype "passive"))
      (node (ref "D2") (pin "1") (pinfunction "A_1") (pintype "passive"))
      (node (ref "JP1") (pin "7") (pinfunction "7_7") (pintype "passive"))
      (node (ref "JP4") (pin "14") (pinfunction "14_14") (pintype "passive"))
      (node (ref "JP6") (pin "1") (pinfunction "1_1") (pintype "passive"))
      (node (ref "JP6") (pin "2") (pinfunction "2_2") (pintype "passive"))
      (node (ref "Q4") (pin "2") (pinfunction "E_2") (pintype "passive"))
      (node (ref "R18") (pin "2") (pinfunction "2_2") (pintype "passive"))
      (node (ref "R19") (pin "1") (pinfunction "1_1") (pintype "passive"))
      (node (ref "R23") (pin "1") (pinfunction "1_1") (pintype "passive"))
      (node (ref "U1") (pin "6") (pinfunction "Vss_6") (pintype "passive"))
      (node (ref "U1") (pin "9") (pinfunction "Vss_9") (pintype "passive"))
      (node (ref "U11") (pin "2") (pinfunction "GND_2") (pintype "passive"))
      (node (ref "U11") (pin "8") (pinfunction "S_8") (pintype "passive"))
      (node (ref "U13") (pin "11") (pinfunction "Vssa_11") (pintype "passive"))
      (node (ref "U13") (pin "15") (pinfunction "Vss_15") (pintype "passive"))
      (node (ref "U13") (pin "31") (pinfunction "Vss_31") (pintype "passive"))
      (node (ref "U13") (pin "41") (pinfunction "Vss_41") (pintype "passive"))
      (node (ref "U13") (pin "55") (pinfunction "Vss_55") (pintype "passive"))
      (node (ref "U13") (pin "72") (pinfunction "Vss_72") (pintype "passive"))
      (node (ref "U13") (pin "83") (pinfunction "Vss_83") (pintype "passive"))
      (node (ref "U13") (pin "97") (pinfunction "Vss_97") (pintype "passive"))
      (node (ref "U23") (pin "4") (pinfunction "Vss_4") (pintype "passive"))
      (node (ref "U24") (pin "10") (pinfunction "REF_IN(-)_10") (pintype "passive"))
      (node (ref "U24") (pin "11") (pinfunction "AIN2(-)_11") (pintype "passive"))
      (node (ref "U24") (pin "16") (pinfunction "GND_16") (pintype "passive"))
      (node (ref "U24") (pin "8") (pinfunction "AIN1(-)_8") (pintype "passive"))
      (node (ref "U5") (pin "2") (pinfunction "GND_2") (pintype "power_in"))
    )
    (net (code "114") (name "Net-(A1-Pad2)") (class "Default")
      (node (ref "A1") (pin "2") (pinfunction "2_2") (pintype "passive"))
      (node (ref "C3") (pin "1") (pinfunction "1_1") (pintype "passive"))
      (node (ref "R16") (pin "1") (pinfunction "1_1") (pintype "passive"))
      (node (ref "R19") (pin "2") (pinfunction "2_2") (pintype "passive"))
    )
    (net (code "115") (name "Net-(Q4-B)") (class "Default")
      (node (ref "Q4") (pin "1") (pinfunction "B_1") (pintype "passive"))
      (node (ref "R22") (pin "2") (pinfunction "2_2") (pintype "passive"))
      (node (ref "R23") (pin "2") (pinfunction "2_2") (pintype "passive"))
    )
    (net (code "116") (name "Net-(Q4-C)") (class "Default")
      (node (ref "A1") (pin "1") (pinfunction "1_1") (pintype "passive"))
      (node (ref "Q4") (pin "3") (pinfunction "C_3") (pintype "passive"))
    )
    (net (code "117") (name "Net-(U1-XTAL1)") (class "Default")
      (node (ref "C201") (pin "2") (pinfunction "2_2") (pintype "passive"))
      (node (ref "U1") (pin "15") (pinfunction "XTAL1_15") (pintype "passive"))
      (node (ref "Y2") (pin "1") (pinfunction "OSC1_1") (pintype "passive"))
    )
    (net (code "118") (name "Net-(U1-XTAL2)") (class "Default")
      (node (ref "C200") (pin "2") (pinfunction "2_2") (pintype "passive"))
      (node (ref "U1") (pin "16") (pinfunction "XTAL2_16") (pintype "passive"))
      (node (ref "Y2") (pin "2") (pinfunction "OSC2_2") (pintype "passive"))
    )
    (net (code "119") (name "Net-(U13-RTCX1)") (class "Default")
      (node (ref "C35") (pin "2") (pinfunction "2_2") (pintype "passive"))
      (node (ref "U13") (pin "16") (pinfunction "RTCX1_16") (pintype "passive"))
      (node (ref "Y1") (pin "2") (pinfunction "OSC2_2") (pintype "passive"))
    )
    (net (code "120") (name "Net-(U13-RTCX2)") (class "Default")
      (node (ref "C36") (pin "2") (pinfunction "2_2") (pintype "passive"))
      (node (ref "U13") (pin "18") (pinfunction "RTCX2_18") (pintype "passive"))
      (node (ref "Y1") (pin "1") (pinfunction "OSC1_1") (pintype "passive"))
    )
    (net (code "121") (name "Net-(U13-XTAL1)") (class "Default")
      (node (ref "C52") (pin "2") (pinfunction "2_2") (pintype "passive"))
      (node (ref "U13") (pin "22") (pinfunction "XTAL1_22") (pintype "passive"))
      (node (ref "Y3") (pin "2") (pinfunction "OSC2_2") (pintype "passive"))
    )
    (net (code "122") (name "Net-(U13-XTAL2)") (class "Default")
      (node (ref "C51") (pin "2") (pinfunction "2_2") (pintype "passive"))
      (node (ref "U13") (pin "23") (pinfunction "XTAL2_23") (pintype "passive"))
      (node (ref "Y3") (pin "1") (pinfunction "OSC1_1") (pintype "passive"))
    )
    (net (code "123") (name "Net-(U23-~{HOLD})") (class "Default")
      (node (ref "R96") (pin "2") (pinfunction "2_2") (pintype "passive"))
      (node (ref "U23") (pin "7") (pinfunction "~{HOLD}_7") (pintype "passive"))
    )
    (net (code "124") (name "Net-(U23-~{WP})") (class "Default")
      (node (ref "R95") (pin "1") (pinfunction "1_1") (pintype "passive"))
      (node (ref "U23") (pin "3") (pinfunction "~{WP}_3") (pintype "passive"))
    )
    (net (code "125") (name "Net-(U24-MCLK_IN)") (class "Default")
      (node (ref "C50") (pin "2") (pinfunction "2_2") (pintype "passive"))
      (node (ref "U24") (pin "2") (pinfunction "MCLK_IN_2") (pintype "passive"))
      (node (ref "Y4") (pin "1") (pinfunction "OSC1_1") (pintype "passive"))
    )
    (net (code "126") (name "Net-(U24-MCLK_OUT)") (class "Default")
      (node (ref "C53") (pin "2") (pinfunction "2_2") (pintype "passive"))
      (node (ref "U24") (pin "3") (pinfunction "MCLK_OUT_3") (pintype "passive"))
      (node (ref "Y4") (pin "2") (pinfunction "OSC2_2") (pintype "passive"))
    )
    (net (code "127") (name "Vbat") (class "Default")
      (node (ref "JP1") (pin "6") (pinfunction "6_6") (pintype "passive"))
      (node (ref "U13") (pin "19") (pinfunction "VBAT_19") (pintype "passive"))
    )
    (net (code "128") (name "Vref") (class "Default")
      (node (ref "U13") (pin "10") (pinfunction "Vdda_10") (pintype "passive"))
      (node (ref "U13") (pin "12") (pinfunction "VREF_12") (pintype "passive"))
      (node (ref "U24") (pin "9") (pinfunction "REF_IN(+)_9") (pintype "passive"))
      (node (ref "U5") (pin "5") (pinfunction "OUT_5") (pintype "power_in"))
    )
    (net (code "129") (name "unconnected-(JP4-Pad30)") (class "Default")
      (node (ref "JP4") (pin "30") (pinfunction "30_30") (pintype "passive"))
    )
    (net (code "130") (name "unconnected-(JP6-Pad10)") (class "Default")
      (node (ref "JP6") (pin "10") (pinfunction "10_10") (pintype "passive"))
    )
    (net (code "131") (name "unconnected-(R15-Pad1)") (class "Default")
      (node (ref "R15") (pin "1") (pinfunction "1_1") (pintype "passive"))
    )
    (net (code "132") (name "unconnected-(U1-SCLK-Pad5)") (class "Default")
      (node (ref "U1") (pin "5") (pinfunction "SCLK_5") (pintype "passive"))
    )
    (net (code "133") (name "unconnected-(U1-SI-Pad3)") (class "Default")
      (node (ref "U1") (pin "3") (pinfunction "SI_3") (pintype "passive"))
    )
    (net (code "134") (name "unconnected-(U1-SO-Pad4)") (class "Default")
      (node (ref "U1") (pin "4") (pinfunction "SO_4") (pintype "passive"))
    )
    (net (code "135") (name "unconnected-(U1-~{CS}-Pad2)") (class "Default")
      (node (ref "U1") (pin "2") (pinfunction "~{CS}_2") (pintype "passive"))
    )
    (net (code "136") (name "unconnected-(U1-~{CTS}-Pad11)") (class "Default")
      (node (ref "U1") (pin "11") (pinfunction "~{CTS}_11") (pintype "passive"))
    )
    (net (code "137") (name "unconnected-(U1-~{IRQ}-Pad7)") (class "Default")
      (node (ref "U1") (pin "7") (pinfunction "~{IRQ}_7") (pintype "passive"))
    )
    (net (code "138") (name "unconnected-(U1-~{SPI}-Pad8)") (class "Default")
      (node (ref "U1") (pin "8") (pinfunction "~{SPI}_8") (pintype "passive"))
    )
    (net (code "139") (name "unconnected-(U5-NC-Pad4)") (class "Default")
      (node (ref "U5") (pin "4") (pinfunction "NC_4") (pintype "passive"))
    )
    (net (code "140") (name "unconnected-(U11-Vref-Pad5)") (class "Default")
      (node (ref "U11") (pin "5") (pinfunction "Vref_5") (pintype "passive"))
    )
    (net (code "141") (name "unconnected-(U13-RTCK-Pad100)") (class "Default")
      (node (ref "U13") (pin "100") (pinfunction "RTCK_100") (pintype "passive"))
    )
    (net (code "142") (name "unconnected-(U13-TCK-Pad5)") (class "Default")
      (node (ref "U13") (pin "5") (pinfunction "TCK_5") (pintype "passive"))
    )
    (net (code "143") (name "unconnected-(U13-TDI-Pad2)") (class "Default")
      (node (ref "U13") (pin "2") (pinfunction "TDI_2") (pintype "passive"))
    )
    (net (code "144") (name "unconnected-(U13-TDO-Pad1)") (class "Default")
      (node (ref "U13") (pin "1") (pinfunction "TDO_1") (pintype "passive"))
    )
    (net (code "145") (name "unconnected-(U13-TMS-Pad3)") (class "Default")
      (node (ref "U13") (pin "3") (pinfunction "TMS_3") (pintype "passive"))
    )
    (net (code "146") (name "unconnected-(U13-~{RSTOUT}-Pad14)") (class "Default")
      (node (ref "U13") (pin "14") (pinfunction "~{RSTOUT}_14") (pintype "passive"))
    )
    (net (code "147") (name "unconnected-(U13-~{TRST}-Pad4)") (class "Default")
      (node (ref "U13") (pin "4") (pinfunction "~{TRST}_4") (pintype "passive"))
    )
    (net (code "148") (name "unconnected-(U24-~{DRDY}-Pad12)") (class "Default")
      (node (ref "U24") (pin "12") (pinfunction "~{DRDY}_12") (pintype "passive"))
    )
    (net (code "149") (name "unconnected-(X9-Pad1)") (class "Default")
      (node (ref "X9") (pin "1") (pinfunction "1_1") (pintype "passive"))
    )
    (net (code "150") (name "unconnected-(X10-Pad1)") (class "Default")
      (node (ref "X10") (pin "1") (pinfunction "1_1") (pintype "passive"))
    )
    (net (code "151") (name "unconnected-(X11-Pad1)") (class "Default")
      (node (ref "X11") (pin "1") (pinfunction "1_1") (pintype "passive"))
    )
    (net (code "152") (name "unconnected-(X12-Pad1)") (class "Default")
      (node (ref "X12") (pin "1") (pinfunction "1_1") (pintype "passive"))
    )
    (net (code "153") (name "unconnected-(X17-Pad1)") (class "Default")
      (node (ref "X17") (pin "1") (pinfunction "1_1") (pintype "passive"))
    )
    (net (code "154") (name "unconnected-(X18-Pad1)") (class "Default")
      (node (ref "X18") (pin "1") (pinfunction "1_1") (pintype "passive"))
    )
    (net (code "155") (name "unconnected-(X19-Pad1)") (class "Default")
      (node (ref "X19") (pin "1") (pinfunction "1_1") (pintype "passive"))
    )
    (net (code "156") (name "unconnected-(X20-Pad1)") (class "Default")
      (node (ref "X20") (pin "1") (pinfunction "1_1") (pintype "passive"))
    )
  )
)
